# 12_iMX_8X_USB.net
KiCad netlist of a schematic drawn in Altium Designer
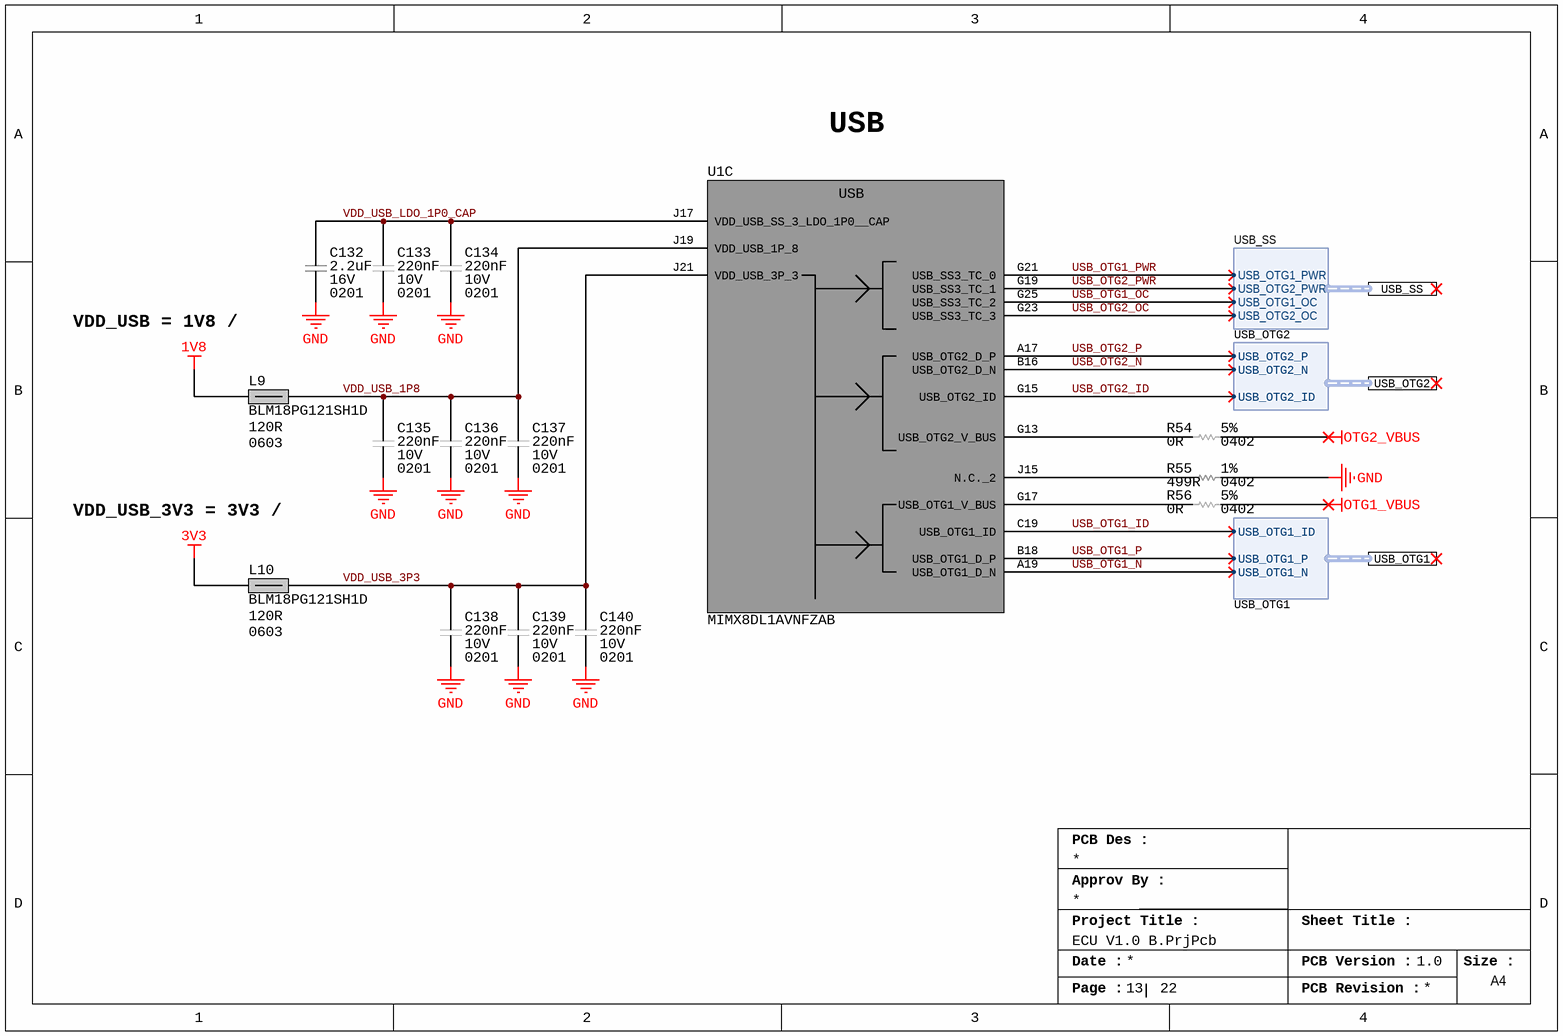
[diagram p0: 12_iMX 8X_USB.SchDoc]

(export (version "E")
  (design (tool "Eeschema 10.0.6"))
  (components
    (comp (ref "C132")
      (value "GRM035R61C225ME01D")
      (footprint "CAP_0201_CAPC0603X03N")
      (description "General Up to 85C Reflow soldering")
      (fields
        (field (name "MANUFACTURER") "Murata")
        (field (name "TOLERANCE") "20%")
        (field (name "CAPACITANCE") "2.2uF")
        (field (name "VOLTAGE RATING") "16V")
        (field (name "CASE/PACKAGE") "0201")
      )
      (libsource (lib "Electronic Devices_LIB") (part "CAP_2.2uF_16V_X5R_0201"))
    )
    (comp (ref "C133")
      (value "LMK063BJ224MP-F")
      (footprint "CAP_0201_CAPC0603X03N")
      (description "Multilayer Ceramic Capacitors (High dielectric type), 10V, 0.22 uF, ± 20 %, 0201, X5R, RoHS")
      (fields
        (field (name "MANUFACTURER") "Taiyo Yuden")
        (field (name "TOLERANCE") "20%")
        (field (name "VOLTAGE RATING (DC)") "10V")
        (field (name "CAPACITANCE") "220nF")
        (field (name "CASE/PACKAGE") "0201")
      )
      (libsource (lib "Electronic Devices_LIB") (part "CAP_0.22UF_10V_X5R_0201"))
    )
    (comp (ref "C134")
      (value "LMK063BJ224MP-F")
      (footprint "CAP_0201_CAPC0603X03N")
      (description "Multilayer Ceramic Capacitors (High dielectric type), 10V, 0.22 uF, ± 20 %, 0201, X5R, RoHS")
      (fields
        (field (name "MANUFACTURER") "Taiyo Yuden")
        (field (name "TOLERANCE") "20%")
        (field (name "VOLTAGE RATING (DC)") "10V")
        (field (name "CAPACITANCE") "220nF")
        (field (name "CASE/PACKAGE") "0201")
      )
      (libsource (lib "Electronic Devices_LIB") (part "CAP_0.22UF_10V_X5R_0201"))
    )
    (comp (ref "C135")
      (value "LMK063BJ224MP-F")
      (footprint "CAP_0201_CAPC0603X03N")
      (description "Multilayer Ceramic Capacitors (High dielectric type), 10V, 0.22 uF, ± 20 %, 0201, X5R, RoHS")
      (fields
        (field (name "MANUFACTURER") "Taiyo Yuden")
        (field (name "TOLERANCE") "20%")
        (field (name "VOLTAGE RATING (DC)") "10V")
        (field (name "CAPACITANCE") "220nF")
        (field (name "CASE/PACKAGE") "0201")
      )
      (libsource (lib "Electronic Devices_LIB") (part "CAP_0.22UF_10V_X5R_0201"))
    )
    (comp (ref "C136")
      (value "LMK063BJ224MP-F")
      (footprint "CAP_0201_CAPC0603X03N")
      (description "Multilayer Ceramic Capacitors (High dielectric type), 10V, 0.22 uF, ± 20 %, 0201, X5R, RoHS")
      (fields
        (field (name "MANUFACTURER") "Taiyo Yuden")
        (field (name "TOLERANCE") "20%")
        (field (name "VOLTAGE RATING (DC)") "10V")
        (field (name "CAPACITANCE") "220nF")
        (field (name "CASE/PACKAGE") "0201")
      )
      (libsource (lib "Electronic Devices_LIB") (part "CAP_0.22UF_10V_X5R_0201"))
    )
    (comp (ref "C137")
      (value "LMK063BJ224MP-F")
      (footprint "CAP_0201_CAPC0603X03N")
      (description "Multilayer Ceramic Capacitors (High dielectric type), 10V, 0.22 uF, ± 20 %, 0201, X5R, RoHS")
      (fields
        (field (name "MANUFACTURER") "Taiyo Yuden")
        (field (name "TOLERANCE") "20%")
        (field (name "VOLTAGE RATING (DC)") "10V")
        (field (name "CAPACITANCE") "220nF")
        (field (name "CASE/PACKAGE") "0201")
      )
      (libsource (lib "Electronic Devices_LIB") (part "CAP_0.22UF_10V_X5R_0201"))
    )
    (comp (ref "C138")
      (value "LMK063BJ224MP-F")
      (footprint "CAP_0201_CAPC0603X03N")
      (description "Multilayer Ceramic Capacitors (High dielectric type), 10V, 0.22 uF, ± 20 %, 0201, X5R, RoHS")
      (fields
        (field (name "MANUFACTURER") "Taiyo Yuden")
        (field (name "TOLERANCE") "20%")
        (field (name "VOLTAGE RATING (DC)") "10V")
        (field (name "CAPACITANCE") "220nF")
        (field (name "CASE/PACKAGE") "0201")
      )
      (libsource (lib "Electronic Devices_LIB") (part "CAP_0.22UF_10V_X5R_0201"))
    )
    (comp (ref "C139")
      (value "LMK063BJ224MP-F")
      (footprint "CAP_0201_CAPC0603X03N")
      (description "Multilayer Ceramic Capacitors (High dielectric type), 10V, 0.22 uF, ± 20 %, 0201, X5R, RoHS")
      (fields
        (field (name "MANUFACTURER") "Taiyo Yuden")
        (field (name "TOLERANCE") "20%")
        (field (name "VOLTAGE RATING (DC)") "10V")
        (field (name "CAPACITANCE") "220nF")
        (field (name "CASE/PACKAGE") "0201")
      )
      (libsource (lib "Electronic Devices_LIB") (part "CAP_0.22UF_10V_X5R_0201"))
    )
    (comp (ref "C140")
      (value "LMK063BJ224MP-F")
      (footprint "CAP_0201_CAPC0603X03N")
      (description "Multilayer Ceramic Capacitors (High dielectric type), 10V, 0.22 uF, ± 20 %, 0201, X5R, RoHS")
      (fields
        (field (name "MANUFACTURER") "Taiyo Yuden")
        (field (name "TOLERANCE") "20%")
        (field (name "VOLTAGE RATING (DC)") "10V")
        (field (name "CAPACITANCE") "220nF")
        (field (name "CASE/PACKAGE") "0201")
      )
      (libsource (lib "Electronic Devices_LIB") (part "CAP_0.22UF_10V_X5R_0201"))
    )
    (comp (ref "L9")
      (value "BLM18PG121SH1D")
      (footprint "IND_0603_INDC1608X08N")
      (description "Ferrite Beads Multi-Layer 120Ohm 25% 100MHz 2A 50mOhm DCR 0603 Automotive Paper T/R")
      (fields
        (field (name "MANUFACTURER") "Murata")
        (field (name "TOLERANCE") "25%")
        (field (name "IMPEDANCE") "120R")
        (field (name "CASE/PACKAGE") "0603")
      )
      (libsource (lib "Electronic Devices_LIB") (part "IND_FERRITE_BEADS_120R_2A_0603_BLM18PG121SH1D"))
    )
    (comp (ref "L10")
      (value "BLM18PG121SH1D")
      (footprint "IND_0603_INDC1608X08N")
      (description "Ferrite Beads Multi-Layer 120Ohm 25% 100MHz 2A 50mOhm DCR 0603 Automotive Paper T/R")
      (fields
        (field (name "MANUFACTURER") "Murata")
        (field (name "TOLERANCE") "25%")
        (field (name "IMPEDANCE") "120R")
        (field (name "CASE/PACKAGE") "0603")
      )
      (libsource (lib "Electronic Devices_LIB") (part "IND_FERRITE_BEADS_120R_2A_0603_BLM18PG121SH1D"))
    )
    (comp (ref "R54")
      (value "ERJ-2GE0R00X")
      (footprint "RES_0402_RESC1005X04N")
      (description "SMD Chip Resistor, Jumper, 0 ohm, 100 mW, 0402 [1005 Metric], Thick Film, General Purpose")
      (fields
        (field (name "MANUFACTURER") "Panasonic")
        (field (name "CASE CODE (IMPERIAL)") "0402")
        (field (name "TOLERANCE") "5%")
        (field (name "RESISTANCE") "0R")
      )
      (libsource (lib "Electronic Devices_LIB") (part "RES_0R_5%_100mW_0402"))
    )
    (comp (ref "R55")
      (value "ERJ-2RKF4990X")
      (footprint "RES_0402_RESC1005X04N")
      (description "SMD Chip Resistor, 499 Ohm, ± 1%, 100 mW, 0402 [1005 Metric], Thick Film, Precision")
      (fields
        (field (name "MANUFACTURER") "Panasonic")
        (field (name "TOLERANCE") "1%")
        (field (name "RESISTANCE") "499R")
        (field (name "CASE/PACKAGE") "0402")
      )
      (libsource (lib "Electronic Devices_LIB") (part "RES_499R_1%_100mW_0402"))
    )
    (comp (ref "R56")
      (value "ERJ-2GE0R00X")
      (footprint "RES_0402_RESC1005X04N")
      (description "SMD Chip Resistor, Jumper, 0 ohm, 100 mW, 0402 [1005 Metric], Thick Film, General Purpose")
      (fields
        (field (name "MANUFACTURER") "Panasonic")
        (field (name "CASE CODE (IMPERIAL)") "0402")
        (field (name "TOLERANCE") "5%")
        (field (name "RESISTANCE") "0R")
      )
      (libsource (lib "Electronic Devices_LIB") (part "RES_0R_5%_100mW_0402"))
    )
    (comp (ref "U1")
      (value "MIMX8DL1AVNFZAB")
      (footprint "MIMX8DL1AVNFZAB")
      (description "I.MX8 Dxl 15SQ / Tray Rohs Compliant: Yes")
      (fields (field (name "MANUFACTURER") "NXP Semiconductors"))
      (libsource (lib "Electronic Devices_LIB") (part "IC_MPU_ARM_1.2GHz_MIMX8DL1AVNFZAB"))
    )
  )
  (nets
    (net (code "4") (name "/USB_OTG1_ID") (class "Default")
      (node (ref "U1") (pin "C19") (pinfunction "USB_OTG1_ID_C19") (pintype "passive+no_connect"))
    )
    (net (code "5") (name "/USB_OTG1_N") (class "Default")
      (node (ref "U1") (pin "A19") (pinfunction "USB_OTG1_D_N_A19") (pintype "passive+no_connect"))
    )
    (net (code "6") (name "/USB_OTG1_OC") (class "Default")
      (node (ref "U1") (pin "G25") (pinfunction "USB_SS3_TC_2_G25") (pintype "passive+no_connect"))
    )
    (net (code "7") (name "/USB_OTG1_P") (class "Default")
      (node (ref "U1") (pin "B18") (pinfunction "USB_OTG1_D_P_B18") (pintype "passive+no_connect"))
    )
    (net (code "8") (name "/USB_OTG1_PWR") (class "Default")
      (node (ref "U1") (pin "G21") (pinfunction "USB_SS3_TC_0_G21") (pintype "passive+no_connect"))
    )
    (net (code "9") (name "/USB_OTG2_ID") (class "Default")
      (node (ref "U1") (pin "G15") (pinfunction "USB_OTG2_ID_G15") (pintype "passive+no_connect"))
    )
    (net (code "10") (name "/USB_OTG2_N") (class "Default")
      (node (ref "U1") (pin "B16") (pinfunction "USB_OTG2_D_N_B16") (pintype "passive+no_connect"))
    )
    (net (code "11") (name "/USB_OTG2_OC") (class "Default")
      (node (ref "U1") (pin "G23") (pinfunction "USB_SS3_TC_3_G23") (pintype "passive+no_connect"))
    )
    (net (code "12") (name "/USB_OTG2_P") (class "Default")
      (node (ref "U1") (pin "A17") (pinfunction "USB_OTG2_D_P_A17") (pintype "passive+no_connect"))
    )
    (net (code "13") (name "/USB_OTG2_PWR") (class "Default")
      (node (ref "U1") (pin "G19") (pinfunction "USB_SS3_TC_1_G19") (pintype "passive+no_connect"))
    )
    (net (code "14") (name "/VDD_USB_1P8") (class "Default")
      (node (ref "C135") (pin "2") (pinfunction "2_2") (pintype "passive"))
      (node (ref "C136") (pin "2") (pinfunction "2_2") (pintype "passive"))
      (node (ref "C137") (pin "2") (pinfunction "2_2") (pintype "passive"))
      (node (ref "L9") (pin "2") (pinfunction "2_2") (pintype "passive"))
      (node (ref "U1") (pin "J19") (pinfunction "VDD_USB_1P_8_J19") (pintype "passive"))
    )
    (net (code "15") (name "/VDD_USB_3P3") (class "Default")
      (node (ref "C138") (pin "2") (pinfunction "2_2") (pintype "passive"))
      (node (ref "C139") (pin "2") (pinfunction "2_2") (pintype "passive"))
      (node (ref "C140") (pin "2") (pinfunction "2_2") (pintype "passive"))
      (node (ref "L10") (pin "2") (pinfunction "2_2") (pintype "passive"))
      (node (ref "U1") (pin "J21") (pinfunction "VDD_USB_3P_3_J21") (pintype "passive"))
    )
    (net (code "16") (name "/VDD_USB_LDO_1P0_CAP") (class "Default")
      (node (ref "C132") (pin "2") (pinfunction "2_2") (pintype "passive"))
      (node (ref "C133") (pin "2") (pinfunction "2_2") (pintype "passive"))
      (node (ref "C134") (pin "2") (pinfunction "2_2") (pintype "passive"))
      (node (ref "U1") (pin "J17") (pinfunction "VDD_USB_SS_3_LDO_1P0__CAP_J17") (pintype "passive"))
    )
    (net (code "20") (name "1V8") (class "Default")
      (node (ref "L9") (pin "1") (pinfunction "1_1") (pintype "passive"))
    )
    (net (code "21") (name "3V3") (class "Default")
      (node (ref "L10") (pin "1") (pinfunction "1_1") (pintype "passive"))
    )
    (net (code "22") (name "GND") (class "Default")
      (node (ref "C132") (pin "1") (pinfunction "1_1") (pintype "passive"))
      (node (ref "C133") (pin "1") (pinfunction "1_1") (pintype "passive"))
      (node (ref "C134") (pin "1") (pinfunction "1_1") (pintype "passive"))
      (node (ref "C135") (pin "1") (pinfunction "1_1") (pintype "passive"))
      (node (ref "C136") (pin "1") (pinfunction "1_1") (pintype "passive"))
      (node (ref "C137") (pin "1") (pinfunction "1_1") (pintype "passive"))
      (node (ref "C138") (pin "1") (pinfunction "1_1") (pintype "passive"))
      (node (ref "C139") (pin "1") (pinfunction "1_1") (pintype "passive"))
      (node (ref "C140") (pin "1") (pinfunction "1_1") (pintype "passive"))
      (node (ref "R55") (pin "2") (pinfunction "2_2") (pintype "passive"))
    )
    (net (code "23") (name "Net-(U1C-N.C._2)") (class "Default")
      (node (ref "R55") (pin "1") (pinfunction "1_1") (pintype "passive"))
      (node (ref "U1") (pin "J15") (pinfunction "N.C._2_J15") (pintype "passive"))
    )
    (net (code "24") (name "Net-(U1C-USB_OTG1_V_BUS)") (class "Default")
      (node (ref "R56") (pin "1") (pinfunction "1_1") (pintype "passive"))
      (node (ref "U1") (pin "G17") (pinfunction "USB_OTG1_V_BUS_G17") (pintype "passive"))
    )
    (net (code "25") (name "Net-(U1C-USB_OTG2_V_BUS)") (class "Default")
      (node (ref "R54") (pin "1") (pinfunction "1_1") (pintype "passive"))
      (node (ref "U1") (pin "G13") (pinfunction "USB_OTG2_V_BUS_G13") (pintype "passive"))
    )
    (net (code "26") (name "OTG1_VBUS") (class "Default")
      (node (ref "R56") (pin "2") (pinfunction "2_2") (pintype "passive"))
    )
    (net (code "27") (name "OTG2_VBUS") (class "Default")
      (node (ref "R54") (pin "2") (pinfunction "2_2") (pintype "passive"))
    )
  )
)
